# Feedback_Sensors.net
KiCad netlist of a schematic drawn in Altium Designer
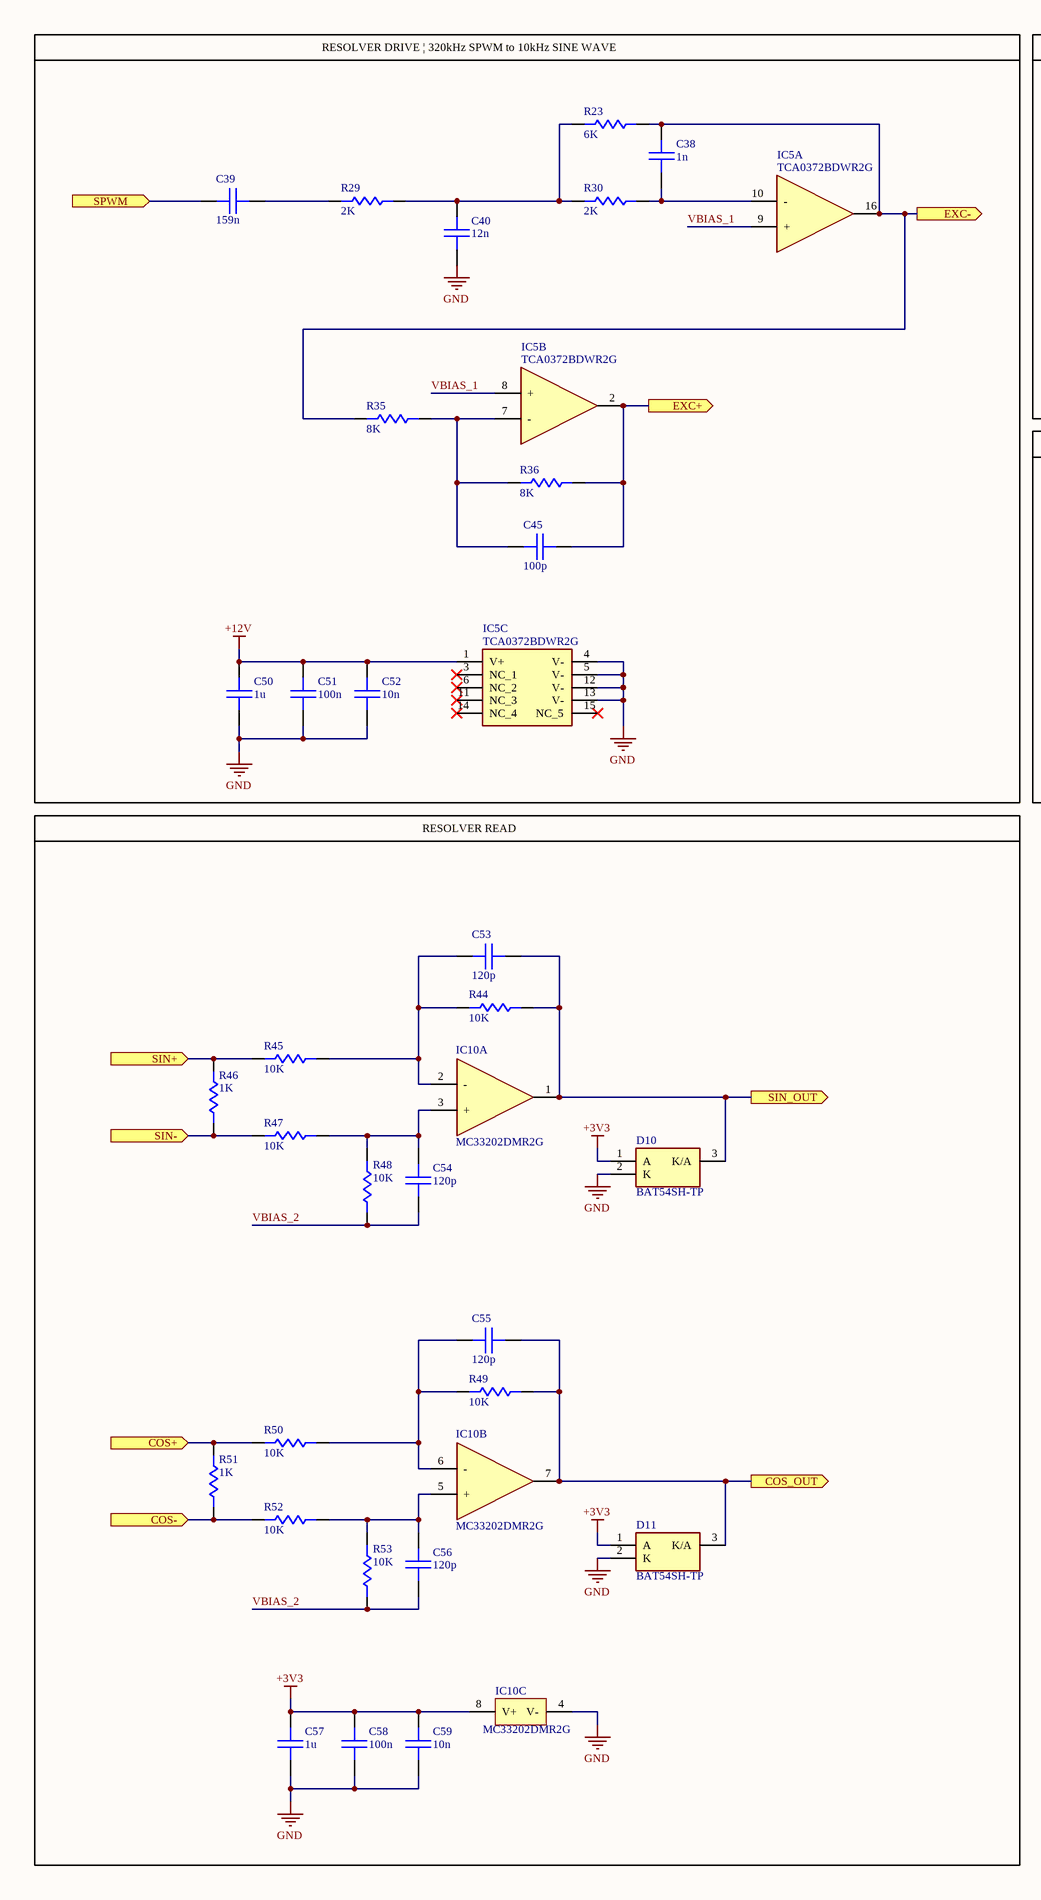
[diagram p0: Feedback_Sensors.SchDoc, left]
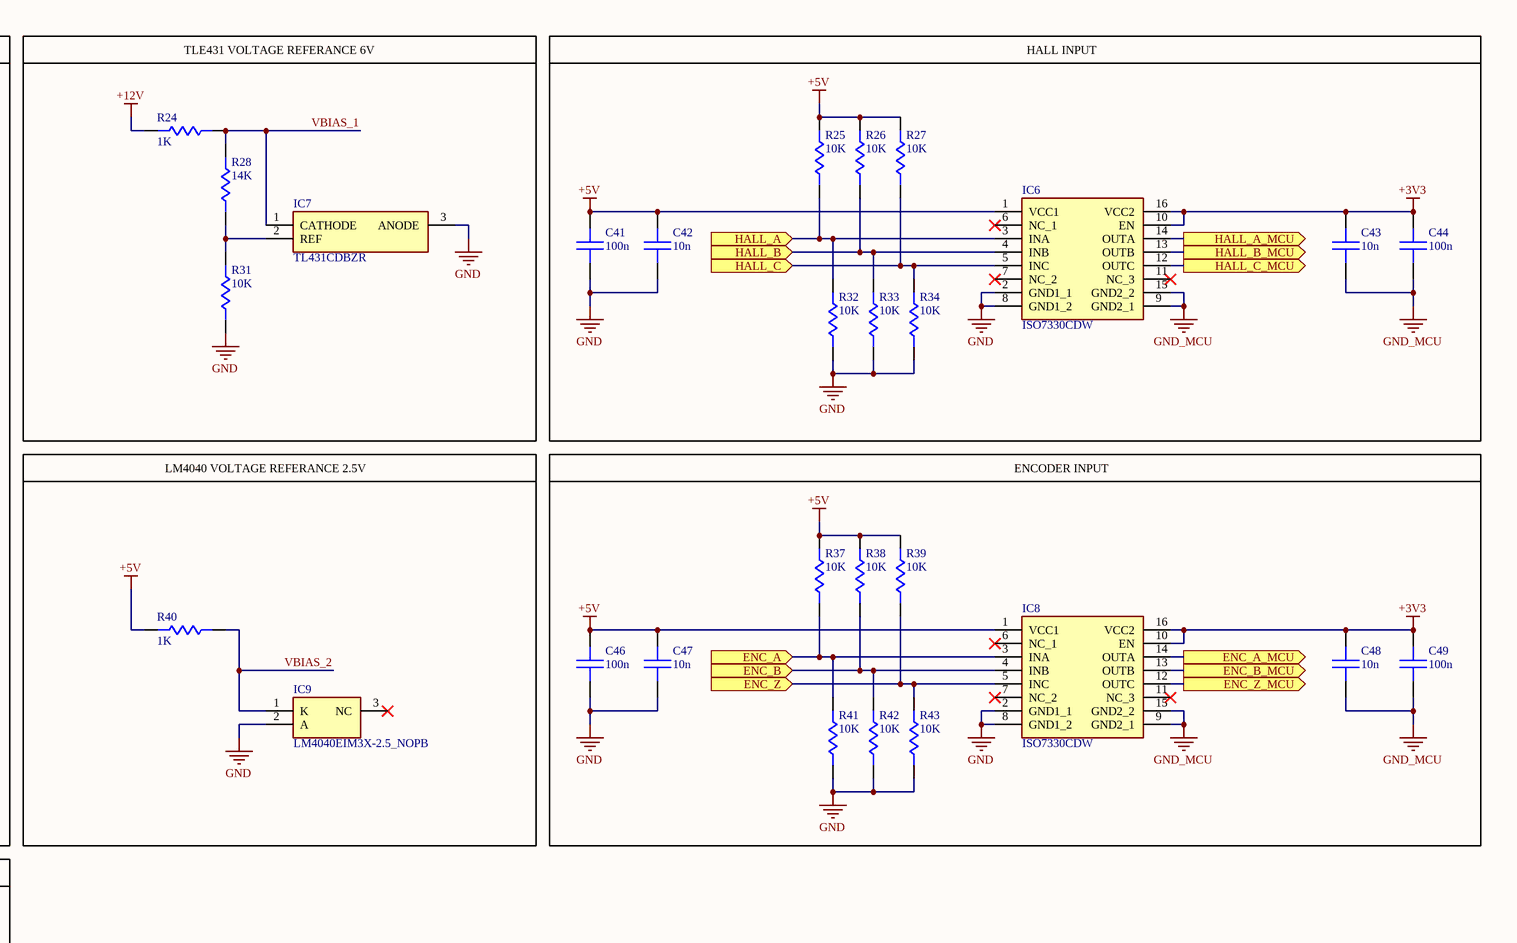
[diagram p1: Feedback_Sensors.SchDoc, right]

(export (version "E")
  (design (tool "Eeschema 10.0.6"))
  (components
    (comp (ref "C38")
      (value "1n")
      (footprint "C_0603")
      (description "SMD Chip Capacitor")
      (libsource (lib "My_Integrated_Lib") (part "CAP"))
    )
    (comp (ref "C39")
      (value "159n")
      (footprint "C_0603")
      (description "SMD Chip Capacitor")
      (libsource (lib "My_Integrated_Lib") (part "CAP"))
    )
    (comp (ref "C40")
      (value "12n")
      (footprint "C_0603")
      (description "SMD Chip Capacitor")
      (libsource (lib "My_Integrated_Lib") (part "CAP"))
    )
    (comp (ref "C41")
      (value "100n")
      (footprint "C_0603")
      (description "SMD Chip Capacitor")
      (libsource (lib "My_Integrated_Lib") (part "CAP"))
    )
    (comp (ref "C42")
      (value "10n")
      (footprint "C_0603")
      (description "SMD Chip Capacitor")
      (libsource (lib "My_Integrated_Lib") (part "CAP"))
    )
    (comp (ref "C43")
      (value "10n")
      (footprint "C_0603")
      (description "SMD Chip Capacitor")
      (libsource (lib "My_Integrated_Lib") (part "CAP"))
    )
    (comp (ref "C44")
      (value "100n")
      (footprint "C_0603")
      (description "SMD Chip Capacitor")
      (libsource (lib "My_Integrated_Lib") (part "CAP"))
    )
    (comp (ref "C45")
      (value "100p")
      (footprint "C_0603")
      (description "SMD Chip Capacitor")
      (libsource (lib "My_Integrated_Lib") (part "CAP"))
    )
    (comp (ref "C46")
      (value "100n")
      (footprint "C_0603")
      (description "SMD Chip Capacitor")
      (libsource (lib "My_Integrated_Lib") (part "CAP"))
    )
    (comp (ref "C47")
      (value "10n")
      (footprint "C_0603")
      (description "SMD Chip Capacitor")
      (libsource (lib "My_Integrated_Lib") (part "CAP"))
    )
    (comp (ref "C48")
      (value "10n")
      (footprint "C_0603")
      (description "SMD Chip Capacitor")
      (libsource (lib "My_Integrated_Lib") (part "CAP"))
    )
    (comp (ref "C49")
      (value "100n")
      (footprint "C_0603")
      (description "SMD Chip Capacitor")
      (libsource (lib "My_Integrated_Lib") (part "CAP"))
    )
    (comp (ref "C50")
      (value "1u")
      (footprint "C_0603")
      (description "SMD Chip Capacitor")
      (libsource (lib "My_Integrated_Lib") (part "CAP"))
    )
    (comp (ref "C51")
      (value "100n")
      (footprint "C_0603")
      (description "SMD Chip Capacitor")
      (libsource (lib "My_Integrated_Lib") (part "CAP"))
    )
    (comp (ref "C52")
      (value "10n")
      (footprint "C_0603")
      (description "SMD Chip Capacitor")
      (libsource (lib "My_Integrated_Lib") (part "CAP"))
    )
    (comp (ref "C53")
      (value "120p")
      (footprint "C_0603")
      (description "SMD Chip Capacitor")
      (libsource (lib "My_Integrated_Lib") (part "CAP"))
    )
    (comp (ref "C54")
      (value "120p")
      (footprint "C_0603")
      (description "SMD Chip Capacitor")
      (libsource (lib "My_Integrated_Lib") (part "CAP"))
    )
    (comp (ref "C55")
      (value "120p")
      (footprint "C_0603")
      (description "SMD Chip Capacitor")
      (libsource (lib "My_Integrated_Lib") (part "CAP"))
    )
    (comp (ref "C56")
      (value "120p")
      (footprint "C_0603")
      (description "SMD Chip Capacitor")
      (libsource (lib "My_Integrated_Lib") (part "CAP"))
    )
    (comp (ref "C57")
      (value "1u")
      (footprint "C_0603")
      (description "SMD Chip Capacitor")
      (libsource (lib "My_Integrated_Lib") (part "CAP"))
    )
    (comp (ref "C58")
      (value "100n")
      (footprint "C_0603")
      (description "SMD Chip Capacitor")
      (libsource (lib "My_Integrated_Lib") (part "CAP"))
    )
    (comp (ref "C59")
      (value "10n")
      (footprint "C_0603")
      (description "SMD Chip Capacitor")
      (libsource (lib "My_Integrated_Lib") (part "CAP"))
    )
    (comp (ref "D10")
      (value "BAT54SH-TP")
      (footprint "SOT95P237X125-3N")
      (description "Schottky Diode")
      (libsource (lib "My_Integrated_Lib") (part "BAT54SH-TP"))
    )
    (comp (ref "D11")
      (value "BAT54SH-TP")
      (footprint "SOT95P237X125-3N")
      (description "Schottky Diode")
      (libsource (lib "My_Integrated_Lib") (part "BAT54SH-TP"))
    )
    (comp (ref "IC5")
      (value "TCA0372BDWR2G")
      (footprint "SOIC127P1030X265-16N")
      (description "Integrated Circuit")
      (fields (field (name "MOUSER PART NUMBER") "863-TCA0372BDWR2G"))
      (libsource (lib "My_Integrated_Lib") (part "TCA0372BDWR2G"))
    )
    (comp (ref "IC6")
      (value "ISO7330CDW")
      (footprint "SOIC127P1030X265-16N")
      (description "Integrated Circuit")
      (fields (field (name "MOUSER PART NUMBER") "595-ISO7330CDW"))
      (libsource (lib "My_Integrated_Lib") (part "ISO7330CDW"))
    )
    (comp (ref "IC7")
      (value "TL431CDBZR")
      (footprint "SOT95P237X112-3N")
      (description "Integrated Circuit")
      (fields (field (name "MOUSER PART NUMBER") "595-TL431CDBZR"))
      (libsource (lib "My_Integrated_Lib") (part "TL431CDBZR"))
    )
    (comp (ref "IC8")
      (value "ISO7330CDW")
      (footprint "SOIC127P1030X265-16N")
      (description "Integrated Circuit")
      (fields (field (name "MOUSER PART NUMBER") "595-ISO7330CDW"))
      (libsource (lib "My_Integrated_Lib") (part "ISO7330CDW"))
    )
    (comp (ref "IC9")
      (value "LM4040EIM3X-2.5_NOPB")
      (footprint "SOT95P237X112-3N")
      (description "Integrated Circuit")
      (fields
        (field (name "MANUFACTURER_PART_NUMBER") "LM4040EIM3X-2.5/NOPB")
        (field (name "MOUSER PART NUMBER") "926-LM4040EIM3X25NPB")
      )
      (libsource (lib "My_Integrated_Lib") (part "LM4040EIM3X-2.5_NOPB"))
    )
    (comp (ref "IC10")
      (value "MC33202DMR2G")
      (footprint "SOP65P490X110-8N")
      (description "Integrated Circuit")
      (fields (field (name "MOUSER PART NUMBER") "863-MC33202DMR2G"))
      (libsource (lib "My_Integrated_Lib") (part "MC33202DMR2G"))
    )
    (comp (ref "R23")
      (value "6K")
      (footprint "R_0603")
      (description "SMD Chip Resistor")
      (libsource (lib "My_Integrated_Lib") (part "RES"))
    )
    (comp (ref "R24")
      (value "1K")
      (footprint "R_0603")
      (description "SMD Chip Resistor")
      (libsource (lib "My_Integrated_Lib") (part "RES"))
    )
    (comp (ref "R25")
      (value "10K")
      (footprint "R_0603")
      (description "SMD Chip Resistor")
      (libsource (lib "My_Integrated_Lib") (part "RES"))
    )
    (comp (ref "R26")
      (value "10K")
      (footprint "R_0603")
      (description "SMD Chip Resistor")
      (libsource (lib "My_Integrated_Lib") (part "RES"))
    )
    (comp (ref "R27")
      (value "10K")
      (footprint "R_0603")
      (description "SMD Chip Resistor")
      (libsource (lib "My_Integrated_Lib") (part "RES"))
    )
    (comp (ref "R28")
      (value "14K")
      (footprint "R_0603")
      (description "SMD Chip Resistor")
      (libsource (lib "My_Integrated_Lib") (part "RES"))
    )
    (comp (ref "R29")
      (value "2K")
      (footprint "R_0603")
      (description "SMD Chip Resistor")
      (libsource (lib "My_Integrated_Lib") (part "RES"))
    )
    (comp (ref "R30")
      (value "2K")
      (footprint "R_0603")
      (description "SMD Chip Resistor")
      (libsource (lib "My_Integrated_Lib") (part "RES"))
    )
    (comp (ref "R31")
      (value "10K")
      (footprint "R_0603")
      (description "SMD Chip Resistor")
      (libsource (lib "My_Integrated_Lib") (part "RES"))
    )
    (comp (ref "R32")
      (value "10K")
      (footprint "R_0603")
      (description "SMD Chip Resistor")
      (libsource (lib "My_Integrated_Lib") (part "RES"))
    )
    (comp (ref "R33")
      (value "10K")
      (footprint "R_0603")
      (description "SMD Chip Resistor")
      (libsource (lib "My_Integrated_Lib") (part "RES"))
    )
    (comp (ref "R34")
      (value "10K")
      (footprint "R_0603")
      (description "SMD Chip Resistor")
      (libsource (lib "My_Integrated_Lib") (part "RES"))
    )
    (comp (ref "R35")
      (value "8K")
      (footprint "R_0603")
      (description "SMD Chip Resistor")
      (libsource (lib "My_Integrated_Lib") (part "RES"))
    )
    (comp (ref "R36")
      (value "8K")
      (footprint "R_0603")
      (description "SMD Chip Resistor")
      (libsource (lib "My_Integrated_Lib") (part "RES"))
    )
    (comp (ref "R37")
      (value "10K")
      (footprint "R_0603")
      (description "SMD Chip Resistor")
      (libsource (lib "My_Integrated_Lib") (part "RES"))
    )
    (comp (ref "R38")
      (value "10K")
      (footprint "R_0603")
      (description "SMD Chip Resistor")
      (libsource (lib "My_Integrated_Lib") (part "RES"))
    )
    (comp (ref "R39")
      (value "10K")
      (footprint "R_0603")
      (description "SMD Chip Resistor")
      (libsource (lib "My_Integrated_Lib") (part "RES"))
    )
    (comp (ref "R40")
      (value "1K")
      (footprint "R_0603")
      (description "SMD Chip Resistor")
      (libsource (lib "My_Integrated_Lib") (part "RES"))
    )
    (comp (ref "R41")
      (value "10K")
      (footprint "R_0603")
      (description "SMD Chip Resistor")
      (libsource (lib "My_Integrated_Lib") (part "RES"))
    )
    (comp (ref "R42")
      (value "10K")
      (footprint "R_0603")
      (description "SMD Chip Resistor")
      (libsource (lib "My_Integrated_Lib") (part "RES"))
    )
    (comp (ref "R43")
      (value "10K")
      (footprint "R_0603")
      (description "SMD Chip Resistor")
      (libsource (lib "My_Integrated_Lib") (part "RES"))
    )
    (comp (ref "R44")
      (value "10K")
      (footprint "R_0603")
      (description "SMD Chip Resistor")
      (libsource (lib "My_Integrated_Lib") (part "RES"))
    )
    (comp (ref "R45")
      (value "10K")
      (footprint "R_0603")
      (description "SMD Chip Resistor")
      (libsource (lib "My_Integrated_Lib") (part "RES"))
    )
    (comp (ref "R46")
      (value "1K")
      (footprint "R_0603")
      (description "SMD Chip Resistor")
      (libsource (lib "My_Integrated_Lib") (part "RES"))
    )
    (comp (ref "R47")
      (value "10K")
      (footprint "R_0603")
      (description "SMD Chip Resistor")
      (libsource (lib "My_Integrated_Lib") (part "RES"))
    )
    (comp (ref "R48")
      (value "10K")
      (footprint "R_0603")
      (description "SMD Chip Resistor")
      (libsource (lib "My_Integrated_Lib") (part "RES"))
    )
    (comp (ref "R49")
      (value "10K")
      (footprint "R_0603")
      (description "SMD Chip Resistor")
      (libsource (lib "My_Integrated_Lib") (part "RES"))
    )
    (comp (ref "R50")
      (value "10K")
      (footprint "R_0603")
      (description "SMD Chip Resistor")
      (libsource (lib "My_Integrated_Lib") (part "RES"))
    )
    (comp (ref "R51")
      (value "1K")
      (footprint "R_0603")
      (description "SMD Chip Resistor")
      (libsource (lib "My_Integrated_Lib") (part "RES"))
    )
    (comp (ref "R52")
      (value "10K")
      (footprint "R_0603")
      (description "SMD Chip Resistor")
      (libsource (lib "My_Integrated_Lib") (part "RES"))
    )
    (comp (ref "R53")
      (value "10K")
      (footprint "R_0603")
      (description "SMD Chip Resistor")
      (libsource (lib "My_Integrated_Lib") (part "RES"))
    )
  )
  (nets
    (net (code "1") (name "+3V3") (class "Default")
      (node (ref "C43") (pin "2") (pinfunction "2_2") (pintype "passive"))
      (node (ref "C44") (pin "2") (pinfunction "2_2") (pintype "passive"))
      (node (ref "C48") (pin "2") (pinfunction "2_2") (pintype "passive"))
      (node (ref "C49") (pin "2") (pinfunction "2_2") (pintype "passive"))
      (node (ref "C57") (pin "2") (pinfunction "2_2") (pintype "passive"))
      (node (ref "C58") (pin "2") (pinfunction "2_2") (pintype "passive"))
      (node (ref "C59") (pin "2") (pinfunction "2_2") (pintype "passive"))
      (node (ref "D10") (pin "1") (pinfunction "A_1") (pintype "passive"))
      (node (ref "D11") (pin "1") (pinfunction "A_1") (pintype "passive"))
      (node (ref "IC10") (pin "8") (pinfunction "V+_8") (pintype "passive"))
      (node (ref "IC6") (pin "10") (pinfunction "EN_10") (pintype "passive"))
      (node (ref "IC6") (pin "16") (pinfunction "VCC2_16") (pintype "passive"))
      (node (ref "IC8") (pin "10") (pinfunction "EN_10") (pintype "passive"))
      (node (ref "IC8") (pin "16") (pinfunction "VCC2_16") (pintype "passive"))
    )
    (net (code "2") (name "+5V") (class "Default")
      (node (ref "C41") (pin "2") (pinfunction "2_2") (pintype "passive"))
      (node (ref "C42") (pin "2") (pinfunction "2_2") (pintype "passive"))
      (node (ref "C46") (pin "2") (pinfunction "2_2") (pintype "passive"))
      (node (ref "C47") (pin "2") (pinfunction "2_2") (pintype "passive"))
      (node (ref "IC6") (pin "1") (pinfunction "VCC1_1") (pintype "passive"))
      (node (ref "IC8") (pin "1") (pinfunction "VCC1_1") (pintype "passive"))
      (node (ref "R25") (pin "1") (pinfunction "1_1") (pintype "passive"))
      (node (ref "R26") (pin "1") (pinfunction "1_1") (pintype "passive"))
      (node (ref "R27") (pin "1") (pinfunction "1_1") (pintype "passive"))
      (node (ref "R37") (pin "1") (pinfunction "1_1") (pintype "passive"))
      (node (ref "R38") (pin "1") (pinfunction "1_1") (pintype "passive"))
      (node (ref "R39") (pin "1") (pinfunction "1_1") (pintype "passive"))
      (node (ref "R40") (pin "2") (pinfunction "2_2") (pintype "passive"))
    )
    (net (code "3") (name "+12V") (class "Default")
      (node (ref "C50") (pin "2") (pinfunction "2_2") (pintype "passive"))
      (node (ref "C51") (pin "2") (pinfunction "2_2") (pintype "passive"))
      (node (ref "C52") (pin "2") (pinfunction "2_2") (pintype "passive"))
      (node (ref "IC5") (pin "1") (pinfunction "V+_1") (pintype "passive"))
      (node (ref "R24") (pin "2") (pinfunction "2_2") (pintype "passive"))
    )
    (net (code "4") (name "/COS+") (class "Default")
      (node (ref "R50") (pin "2") (pinfunction "2_2") (pintype "passive"))
      (node (ref "R51") (pin "2") (pinfunction "2_2") (pintype "passive"))
    )
    (net (code "5") (name "/COS-") (class "Default")
      (node (ref "R51") (pin "1") (pinfunction "1_1") (pintype "passive"))
      (node (ref "R52") (pin "2") (pinfunction "2_2") (pintype "passive"))
    )
    (net (code "6") (name "/COS_OUT") (class "Default")
      (node (ref "C55") (pin "1") (pinfunction "1_1") (pintype "passive"))
      (node (ref "D11") (pin "3") (pinfunction "K/A_3") (pintype "passive"))
      (node (ref "IC10") (pin "7") (pinfunction "OUTPUT_2_7") (pintype "passive"))
      (node (ref "R49") (pin "1") (pinfunction "1_1") (pintype "passive"))
    )
    (net (code "7") (name "/ENC_A") (class "Default")
      (node (ref "IC8") (pin "3") (pinfunction "INA_3") (pintype "passive"))
      (node (ref "R37") (pin "2") (pinfunction "2_2") (pintype "passive"))
      (node (ref "R41") (pin "1") (pinfunction "1_1") (pintype "passive"))
    )
    (net (code "8") (name "/ENC_A_MCU") (class "Default")
      (node (ref "IC8") (pin "14") (pinfunction "OUTA_14") (pintype "passive"))
    )
    (net (code "9") (name "/ENC_B") (class "Default")
      (node (ref "IC8") (pin "4") (pinfunction "INB_4") (pintype "passive"))
      (node (ref "R38") (pin "2") (pinfunction "2_2") (pintype "passive"))
      (node (ref "R42") (pin "1") (pinfunction "1_1") (pintype "passive"))
    )
    (net (code "10") (name "/ENC_B_MCU") (class "Default")
      (node (ref "IC8") (pin "13") (pinfunction "OUTB_13") (pintype "passive"))
    )
    (net (code "11") (name "/ENC_Z") (class "Default")
      (node (ref "IC8") (pin "5") (pinfunction "INC_5") (pintype "passive"))
      (node (ref "R39") (pin "2") (pinfunction "2_2") (pintype "passive"))
      (node (ref "R43") (pin "1") (pinfunction "1_1") (pintype "passive"))
    )
    (net (code "12") (name "/ENC_Z_MCU") (class "Default")
      (node (ref "IC8") (pin "12") (pinfunction "OUTC_12") (pintype "passive"))
    )
    (net (code "13") (name "/EXC+") (class "Default")
      (node (ref "C45") (pin "1") (pinfunction "1_1") (pintype "passive"))
      (node (ref "IC5") (pin "2") (pinfunction "OUTPUT_B_2") (pintype "passive"))
      (node (ref "R36") (pin "1") (pinfunction "1_1") (pintype "passive"))
    )
    (net (code "14") (name "/EXC-") (class "Default")
      (node (ref "C38") (pin "1") (pinfunction "1_1") (pintype "passive"))
      (node (ref "IC5") (pin "16") (pinfunction "OUTPUT_A_16") (pintype "passive"))
      (node (ref "R23") (pin "1") (pinfunction "1_1") (pintype "passive"))
      (node (ref "R35") (pin "2") (pinfunction "2_2") (pintype "passive"))
    )
    (net (code "15") (name "/HALL_A") (class "Default")
      (node (ref "IC6") (pin "3") (pinfunction "INA_3") (pintype "passive"))
      (node (ref "R25") (pin "2") (pinfunction "2_2") (pintype "passive"))
      (node (ref "R32") (pin "1") (pinfunction "1_1") (pintype "passive"))
    )
    (net (code "16") (name "/HALL_A_MCU") (class "Default")
      (node (ref "IC6") (pin "14") (pinfunction "OUTA_14") (pintype "passive"))
    )
    (net (code "17") (name "/HALL_B") (class "Default")
      (node (ref "IC6") (pin "4") (pinfunction "INB_4") (pintype "passive"))
      (node (ref "R26") (pin "2") (pinfunction "2_2") (pintype "passive"))
      (node (ref "R33") (pin "1") (pinfunction "1_1") (pintype "passive"))
    )
    (net (code "18") (name "/HALL_B_MCU") (class "Default")
      (node (ref "IC6") (pin "13") (pinfunction "OUTB_13") (pintype "passive"))
    )
    (net (code "19") (name "/HALL_C") (class "Default")
      (node (ref "IC6") (pin "5") (pinfunction "INC_5") (pintype "passive"))
      (node (ref "R27") (pin "2") (pinfunction "2_2") (pintype "passive"))
      (node (ref "R34") (pin "1") (pinfunction "1_1") (pintype "passive"))
    )
    (net (code "20") (name "/HALL_C_MCU") (class "Default")
      (node (ref "IC6") (pin "12") (pinfunction "OUTC_12") (pintype "passive"))
    )
    (net (code "21") (name "/SIN+") (class "Default")
      (node (ref "R45") (pin "2") (pinfunction "2_2") (pintype "passive"))
      (node (ref "R46") (pin "2") (pinfunction "2_2") (pintype "passive"))
    )
    (net (code "22") (name "/SIN-") (class "Default")
      (node (ref "R46") (pin "1") (pinfunction "1_1") (pintype "passive"))
      (node (ref "R47") (pin "2") (pinfunction "2_2") (pintype "passive"))
    )
    (net (code "23") (name "/SIN_OUT") (class "Default")
      (node (ref "C53") (pin "1") (pinfunction "1_1") (pintype "passive"))
      (node (ref "D10") (pin "3") (pinfunction "K/A_3") (pintype "passive"))
      (node (ref "IC10") (pin "1") (pinfunction "OUTPUT_1_1") (pintype "passive"))
      (node (ref "R44") (pin "1") (pinfunction "1_1") (pintype "passive"))
    )
    (net (code "24") (name "/SPWM") (class "Default")
      (node (ref "C39") (pin "1") (pinfunction "1_1") (pintype "passive"))
    )
    (net (code "25") (name "/VBIAS_1") (class "Default")
      (node (ref "IC5") (pin "8") (pinfunction "+_8") (pintype "passive"))
      (node (ref "IC5") (pin "9") (pinfunction "+_9") (pintype "passive"))
      (node (ref "IC7") (pin "1") (pinfunction "CATHODE_1") (pintype "passive"))
      (node (ref "R24") (pin "1") (pinfunction "1_1") (pintype "passive"))
      (node (ref "R28") (pin "2") (pinfunction "2_2") (pintype "passive"))
    )
    (net (code "26") (name "/VBIAS_2") (class "Default")
      (node (ref "C54") (pin "1") (pinfunction "1_1") (pintype "passive"))
      (node (ref "C56") (pin "1") (pinfunction "1_1") (pintype "passive"))
      (node (ref "IC9") (pin "1") (pinfunction "K_1") (pintype "passive"))
      (node (ref "R40") (pin "1") (pinfunction "1_1") (pintype "passive"))
      (node (ref "R48") (pin "1") (pinfunction "1_1") (pintype "passive"))
      (node (ref "R53") (pin "1") (pinfunction "1_1") (pintype "passive"))
    )
    (net (code "27") (name "GND") (class "Default")
      (node (ref "C40") (pin "2") (pinfunction "2_2") (pintype "passive"))
      (node (ref "C41") (pin "1") (pinfunction "1_1") (pintype "passive"))
      (node (ref "C42") (pin "1") (pinfunction "1_1") (pintype "passive"))
      (node (ref "C46") (pin "1") (pinfunction "1_1") (pintype "passive"))
      (node (ref "C47") (pin "1") (pinfunction "1_1") (pintype "passive"))
      (node (ref "C50") (pin "1") (pinfunction "1_1") (pintype "passive"))
      (node (ref "C51") (pin "1") (pinfunction "1_1") (pintype "passive"))
      (node (ref "C52") (pin "1") (pinfunction "1_1") (pintype "passive"))
      (node (ref "C57") (pin "1") (pinfunction "1_1") (pintype "passive"))
      (node (ref "C58") (pin "1") (pinfunction "1_1") (pintype "passive"))
      (node (ref "C59") (pin "1") (pinfunction "1_1") (pintype "passive"))
      (node (ref "D10") (pin "2") (pinfunction "K_2") (pintype "passive"))
      (node (ref "D11") (pin "2") (pinfunction "K_2") (pintype "passive"))
      (node (ref "IC10") (pin "4") (pinfunction "V-_4") (pintype "passive"))
      (node (ref "IC5") (pin "12") (pinfunction "V-_12") (pintype "passive"))
      (node (ref "IC5") (pin "13") (pinfunction "V-_13") (pintype "passive"))
      (node (ref "IC5") (pin "4") (pinfunction "V-_4") (pintype "passive"))
      (node (ref "IC5") (pin "5") (pinfunction "V-_5") (pintype "passive"))
      (node (ref "IC6") (pin "2") (pinfunction "GND1_1_2") (pintype "passive"))
      (node (ref "IC6") (pin "8") (pinfunction "GND1_2_8") (pintype "passive"))
      (node (ref "IC7") (pin "3") (pinfunction "ANODE_3") (pintype "passive"))
      (node (ref "IC8") (pin "2") (pinfunction "GND1_1_2") (pintype "passive"))
      (node (ref "IC8") (pin "8") (pinfunction "GND1_2_8") (pintype "passive"))
      (node (ref "IC9") (pin "2") (pinfunction "A_2") (pintype "passive"))
      (node (ref "R31") (pin "1") (pinfunction "1_1") (pintype "passive"))
      (node (ref "R32") (pin "2") (pinfunction "2_2") (pintype "passive"))
      (node (ref "R33") (pin "2") (pinfunction "2_2") (pintype "passive"))
      (node (ref "R34") (pin "2") (pinfunction "2_2") (pintype "passive"))
      (node (ref "R41") (pin "2") (pinfunction "2_2") (pintype "passive"))
      (node (ref "R42") (pin "2") (pinfunction "2_2") (pintype "passive"))
      (node (ref "R43") (pin "2") (pinfunction "2_2") (pintype "passive"))
    )
    (net (code "28") (name "GND_MCU") (class "Default")
      (node (ref "C43") (pin "1") (pinfunction "1_1") (pintype "passive"))
      (node (ref "C44") (pin "1") (pinfunction "1_1") (pintype "passive"))
      (node (ref "C48") (pin "1") (pinfunction "1_1") (pintype "passive"))
      (node (ref "C49") (pin "1") (pinfunction "1_1") (pintype "passive"))
      (node (ref "IC6") (pin "15") (pinfunction "GND2_2_15") (pintype "passive"))
      (node (ref "IC6") (pin "9") (pinfunction "GND2_1_9") (pintype "passive"))
      (node (ref "IC8") (pin "15") (pinfunction "GND2_2_15") (pintype "passive"))
      (node (ref "IC8") (pin "9") (pinfunction "GND2_1_9") (pintype "passive"))
    )
    (net (code "29") (name "Net-(C39-Pad2)") (class "Default")
      (node (ref "C39") (pin "2") (pinfunction "2_2") (pintype "passive"))
      (node (ref "R29") (pin "2") (pinfunction "2_2") (pintype "passive"))
    )
    (net (code "30") (name "Net-(C40-Pad1)") (class "Default")
      (node (ref "C40") (pin "1") (pinfunction "1_1") (pintype "passive"))
      (node (ref "R23") (pin "2") (pinfunction "2_2") (pintype "passive"))
      (node (ref "R29") (pin "1") (pinfunction "1_1") (pintype "passive"))
      (node (ref "R30") (pin "2") (pinfunction "2_2") (pintype "passive"))
    )
    (net (code "31") (name "Net-(IC5A--)") (class "Default")
      (node (ref "C38") (pin "2") (pinfunction "2_2") (pintype "passive"))
      (node (ref "IC5") (pin "10") (pinfunction "-_10") (pintype "passive"))
      (node (ref "R30") (pin "1") (pinfunction "1_1") (pintype "passive"))
    )
    (net (code "32") (name "Net-(IC5B--)") (class "Default")
      (node (ref "C45") (pin "2") (pinfunction "2_2") (pintype "passive"))
      (node (ref "IC5") (pin "7") (pinfunction "-_7") (pintype "passive"))
      (node (ref "R35") (pin "1") (pinfunction "1_1") (pintype "passive"))
      (node (ref "R36") (pin "2") (pinfunction "2_2") (pintype "passive"))
    )
    (net (code "33") (name "Net-(IC7A-REF)") (class "Default")
      (node (ref "IC7") (pin "2") (pinfunction "REF_2") (pintype "passive"))
      (node (ref "R28") (pin "1") (pinfunction "1_1") (pintype "passive"))
      (node (ref "R31") (pin "2") (pinfunction "2_2") (pintype "passive"))
    )
    (net (code "34") (name "Net-(IC10A-+)") (class "Default")
      (node (ref "C54") (pin "2") (pinfunction "2_2") (pintype "passive"))
      (node (ref "IC10") (pin "3") (pinfunction "+_3") (pintype "passive"))
      (node (ref "R47") (pin "1") (pinfunction "1_1") (pintype "passive"))
      (node (ref "R48") (pin "2") (pinfunction "2_2") (pintype "passive"))
    )
    (net (code "35") (name "Net-(IC10A--)") (class "Default")
      (node (ref "C53") (pin "2") (pinfunction "2_2") (pintype "passive"))
      (node (ref "IC10") (pin "2") (pinfunction "-_2") (pintype "passive"))
      (node (ref "R44") (pin "2") (pinfunction "2_2") (pintype "passive"))
      (node (ref "R45") (pin "1") (pinfunction "1_1") (pintype "passive"))
    )
    (net (code "36") (name "Net-(IC10B-+)") (class "Default")
      (node (ref "C56") (pin "2") (pinfunction "2_2") (pintype "passive"))
      (node (ref "IC10") (pin "5") (pinfunction "+_5") (pintype "passive"))
      (node (ref "R52") (pin "1") (pinfunction "1_1") (pintype "passive"))
      (node (ref "R53") (pin "2") (pinfunction "2_2") (pintype "passive"))
    )
    (net (code "37") (name "Net-(IC10B--)") (class "Default")
      (node (ref "C55") (pin "2") (pinfunction "2_2") (pintype "passive"))
      (node (ref "IC10") (pin "6") (pinfunction "-_6") (pintype "passive"))
      (node (ref "R49") (pin "2") (pinfunction "2_2") (pintype "passive"))
      (node (ref "R50") (pin "1") (pinfunction "1_1") (pintype "passive"))
    )
    (net (code "38") (name "unconnected-(IC5C-NC_1-Pad3)") (class "Default")
      (node (ref "IC5") (pin "3") (pinfunction "NC_1_3") (pintype "passive+no_connect"))
    )
    (net (code "39") (name "unconnected-(IC5C-NC_2-Pad6)") (class "Default")
      (node (ref "IC5") (pin "6") (pinfunction "NC_2_6") (pintype "passive+no_connect"))
    )
    (net (code "40") (name "unconnected-(IC5C-NC_3-Pad11)") (class "Default")
      (node (ref "IC5") (pin "11") (pinfunction "NC_3_11") (pintype "passive+no_connect"))
    )
    (net (code "41") (name "unconnected-(IC5C-NC_4-Pad14)") (class "Default")
      (node (ref "IC5") (pin "14") (pinfunction "NC_4_14") (pintype "passive+no_connect"))
    )
    (net (code "42") (name "unconnected-(IC5C-NC_5-Pad15)") (class "Default")
      (node (ref "IC5") (pin "15") (pinfunction "NC_5_15") (pintype "passive+no_connect"))
    )
    (net (code "43") (name "unconnected-(IC6-NC_1-Pad6)") (class "Default")
      (node (ref "IC6") (pin "6") (pinfunction "NC_1_6") (pintype "passive+no_connect"))
    )
    (net (code "44") (name "unconnected-(IC6-NC_2-Pad7)") (class "Default")
      (node (ref "IC6") (pin "7") (pinfunction "NC_2_7") (pintype "passive+no_connect"))
    )
    (net (code "45") (name "unconnected-(IC6-NC_3-Pad11)") (class "Default")
      (node (ref "IC6") (pin "11") (pinfunction "NC_3_11") (pintype "passive+no_connect"))
    )
    (net (code "46") (name "unconnected-(IC8-NC_1-Pad6)") (class "Default")
      (node (ref "IC8") (pin "6") (pinfunction "NC_1_6") (pintype "passive+no_connect"))
    )
    (net (code "47") (name "unconnected-(IC8-NC_2-Pad7)") (class "Default")
      (node (ref "IC8") (pin "7") (pinfunction "NC_2_7") (pintype "passive+no_connect"))
    )
    (net (code "48") (name "unconnected-(IC8-NC_3-Pad11)") (class "Default")
      (node (ref "IC8") (pin "11") (pinfunction "NC_3_11") (pintype "passive+no_connect"))
    )
    (net (code "49") (name "unconnected-(IC9-NC-Pad3)") (class "Default")
      (node (ref "IC9") (pin "3") (pinfunction "NC_3") (pintype "passive+no_connect"))
    )
  )
)
